# Motor_controllers.net
KiCad netlist of a schematic drawn in Altium Designer
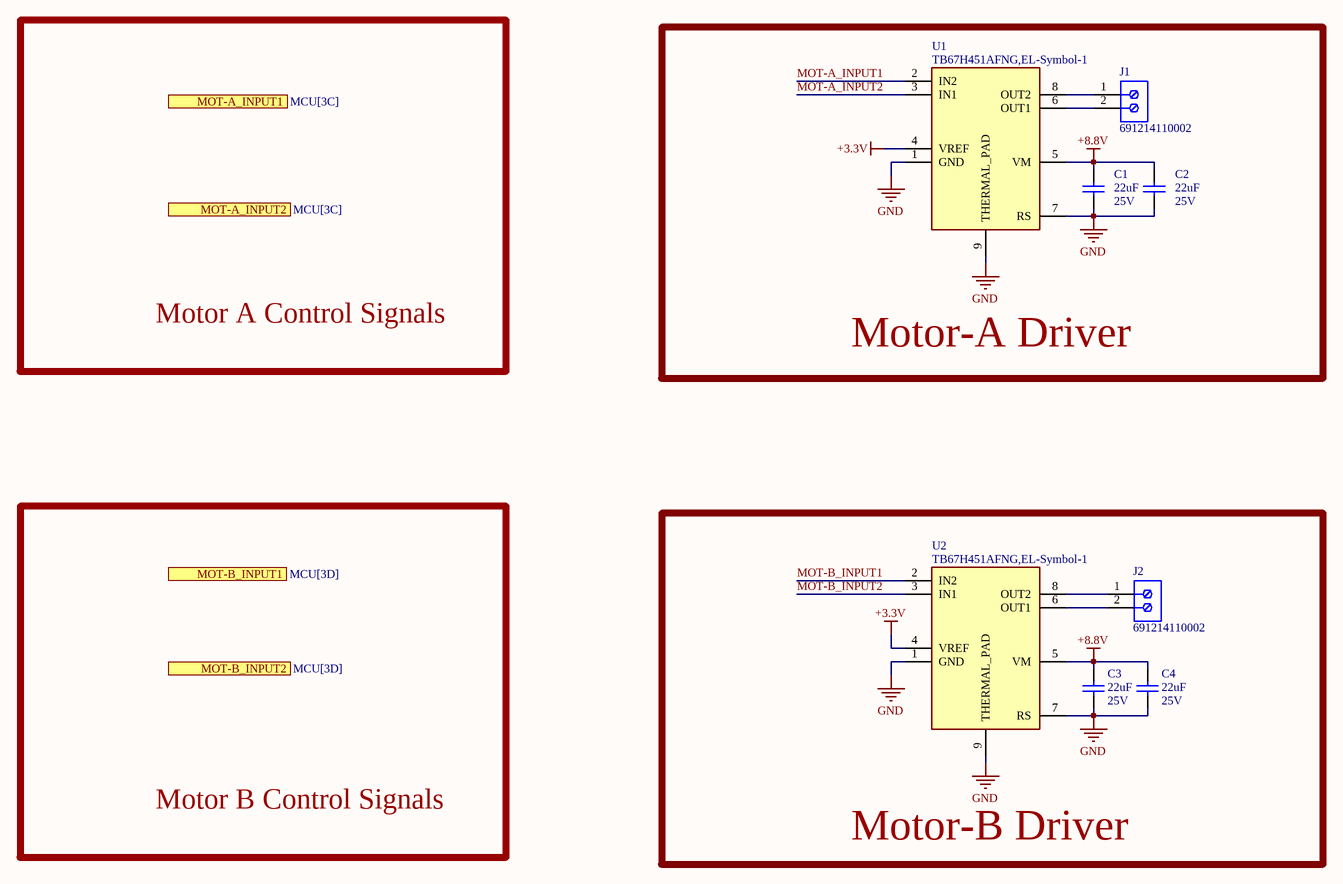
[diagram p0: Motor controllers.SchDoc]

(export (version "E")
  (design (tool "Eeschema 10.0.6"))
  (components
    (comp (ref "C1")
      (value "22uF")
      (footprint "CAPC320160X160_CL31H-0_2_M")
      (fields (field (name "RATED DC VOLTAGE (URDC)") "25V") (field (name "Comment") "22uF 25V 1206"))
      (libsource (lib "2025 Bright Manufacturing Challenge") (part "CAP"))
    )
    (comp (ref "C2")
      (value "22uF")
      (footprint "CAPC320160X160_CL31H-0_2_M")
      (fields (field (name "RATED DC VOLTAGE (URDC)") "25V") (field (name "Comment") "22uF 25V 1206"))
      (libsource (lib "2025 Bright Manufacturing Challenge") (part "CAP"))
    )
    (comp (ref "C3")
      (value "22uF")
      (footprint "CAPC320160X160_CL31H-0_2_M")
      (fields (field (name "RATED DC VOLTAGE (URDC)") "25V") (field (name "Comment") "22uF 25V 1206"))
      (libsource (lib "2025 Bright Manufacturing Challenge") (part "CAP"))
    )
    (comp (ref "C4")
      (value "22uF")
      (footprint "CAPC320160X160_CL31H-0_2_M")
      (fields (field (name "RATED DC VOLTAGE (URDC)") "25V") (field (name "Comment") "22uF 25V 1206"))
      (libsource (lib "2025 Bright Manufacturing Challenge") (part "CAP"))
    )
    (comp (ref "J1")
      (value "691214110002")
      (footprint "691214110002")
      (description "Barrier Strip Terminal Block")
      (libsource (lib "2025 Bright Manufacturing Challenge") (part "TBL - 1R - 02P - Screw"))
    )
    (comp (ref "J2")
      (value "691214110002")
      (footprint "691214110002")
      (description "Barrier Strip Terminal Block")
      (libsource (lib "2025 Bright Manufacturing Challenge") (part "TBL - 1R - 02P - Screw"))
    )
    (comp (ref "U1")
      (value "TB67H451AFNG,EL-Symbol-1")
      (footprint "SOIC127P600X170-9N")
      (description "PWM Chopper Type DC Brushed Motor Driver 24V 8-Pin HSOP")
      (libsource (lib "2025 Bright Manufacturing Challenge") (part "TB67H451AFNG,EL-Symbol-1"))
    )
    (comp (ref "U2")
      (value "TB67H451AFNG,EL-Symbol-1")
      (footprint "SOIC127P600X170-9N")
      (description "PWM Chopper Type DC Brushed Motor Driver 24V 8-Pin HSOP")
      (libsource (lib "2025 Bright Manufacturing Challenge") (part "TB67H451AFNG,EL-Symbol-1"))
    )
  )
  (nets
    (net (code "1") (name "+3.3V") (class "Default")
      (node (ref "U1") (pin "4") (pinfunction "VREF_4") (pintype "passive"))
      (node (ref "U2") (pin "4") (pinfunction "VREF_4") (pintype "passive"))
    )
    (net (code "2") (name "+8.8V") (class "Default")
      (node (ref "C1") (pin "2") (pinfunction "2_2") (pintype "passive"))
      (node (ref "C2") (pin "2") (pinfunction "2_2") (pintype "passive"))
      (node (ref "C3") (pin "2") (pinfunction "2_2") (pintype "passive"))
      (node (ref "C4") (pin "2") (pinfunction "2_2") (pintype "passive"))
      (node (ref "U1") (pin "5") (pinfunction "VM_5") (pintype "passive"))
      (node (ref "U2") (pin "5") (pinfunction "VM_5") (pintype "passive"))
    )
    (net (code "3") (name "/MOT-A_INPUT1") (class "Default")
      (node (ref "U1") (pin "2") (pinfunction "IN2_2") (pintype "passive"))
    )
    (net (code "4") (name "/MOT-A_INPUT2") (class "Default")
      (node (ref "U1") (pin "3") (pinfunction "IN1_3") (pintype "passive"))
    )
    (net (code "5") (name "/MOT-B_INPUT1") (class "Default")
      (node (ref "U2") (pin "2") (pinfunction "IN2_2") (pintype "passive"))
    )
    (net (code "6") (name "/MOT-B_INPUT2") (class "Default")
      (node (ref "U2") (pin "3") (pinfunction "IN1_3") (pintype "passive"))
    )
    (net (code "7") (name "GND") (class "Default")
      (node (ref "C1") (pin "1") (pinfunction "1_1") (pintype "passive"))
      (node (ref "C2") (pin "1") (pinfunction "1_1") (pintype "passive"))
      (node (ref "C3") (pin "1") (pinfunction "1_1") (pintype "passive"))
      (node (ref "C4") (pin "1") (pinfunction "1_1") (pintype "passive"))
      (node (ref "U1") (pin "1") (pinfunction "GND_1") (pintype "passive"))
      (node (ref "U1") (pin "7") (pinfunction "RS_7") (pintype "passive"))
      (node (ref "U1") (pin "9") (pinfunction "THERMAL_PAD_9") (pintype "passive"))
      (node (ref "U2") (pin "1") (pinfunction "GND_1") (pintype "passive"))
      (node (ref "U2") (pin "7") (pinfunction "RS_7") (pintype "passive"))
      (node (ref "U2") (pin "9") (pinfunction "THERMAL_PAD_9") (pintype "passive"))
    )
    (net (code "8") (name "Net-(U1-OUT1)") (class "Default")
      (node (ref "J1") (pin "2") (pinfunction "2_2") (pintype "passive"))
      (node (ref "U1") (pin "6") (pinfunction "OUT1_6") (pintype "passive"))
    )
    (net (code "9") (name "Net-(U1-OUT2)") (class "Default")
      (node (ref "J1") (pin "1") (pinfunction "1_1") (pintype "passive"))
      (node (ref "U1") (pin "8") (pinfunction "OUT2_8") (pintype "passive"))
    )
    (net (code "10") (name "Net-(U2-OUT1)") (class "Default")
      (node (ref "J2") (pin "2") (pinfunction "2_2") (pintype "passive"))
      (node (ref "U2") (pin "6") (pinfunction "OUT1_6") (pintype "passive"))
    )
    (net (code "11") (name "Net-(U2-OUT2)") (class "Default")
      (node (ref "J2") (pin "1") (pinfunction "1_1") (pintype "passive"))
      (node (ref "U2") (pin "8") (pinfunction "OUT2_8") (pintype "passive"))
    )
  )
)
